# BAL3S.net
KiCad netlist of a schematic drawn in EAGLE
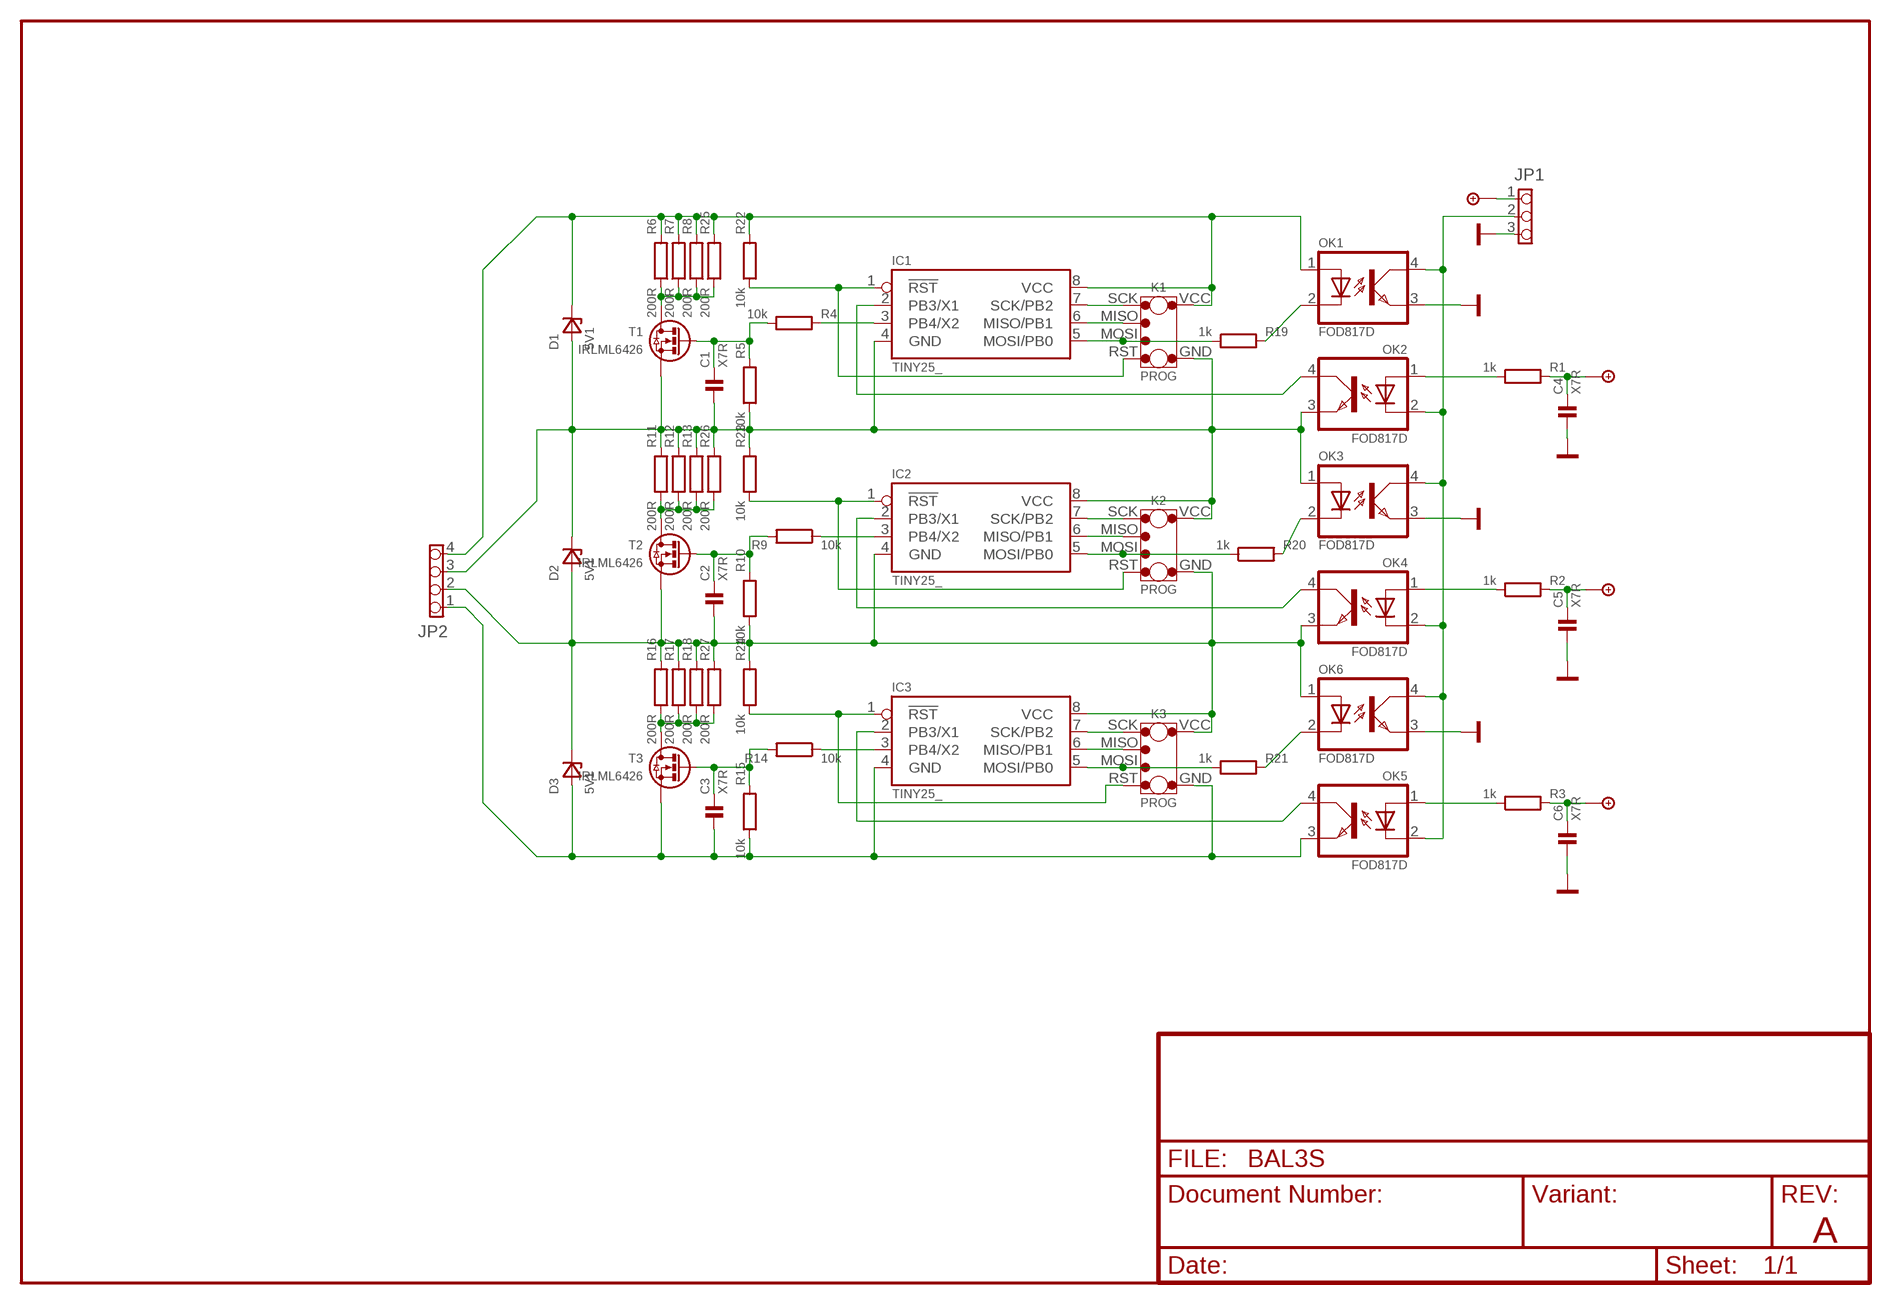
[diagram p0: schematic, sheet 1]

(export (version "E")
  (design (tool "Eeschema 10.0.6"))
  (components
    (comp (ref "C1")
      (value "C0805")
      (footprint "eagle-import:0805")
      (libsource (lib "eagle-import") (part "C0805"))
    )
    (comp (ref "C2")
      (value "C0805")
      (footprint "eagle-import:0805")
      (libsource (lib "eagle-import") (part "C0805"))
    )
    (comp (ref "C3")
      (value "C0805")
      (footprint "eagle-import:0805")
      (libsource (lib "eagle-import") (part "C0805"))
    )
    (comp (ref "C4")
      (value "C0805")
      (footprint "eagle-import:0805")
      (libsource (lib "eagle-import") (part "C0805"))
    )
    (comp (ref "C5")
      (value "C0805")
      (footprint "eagle-import:0805")
      (libsource (lib "eagle-import") (part "C0805"))
    )
    (comp (ref "C6")
      (value "C0805")
      (footprint "eagle-import:0805")
      (libsource (lib "eagle-import") (part "C0805"))
    )
    (comp (ref "D1")
      (value "5V1")
      (footprint "eagle-import:D_MLL41")
      (libsource (lib "eagle-import") (part "D_ZENER_MLL41"))
    )
    (comp (ref "D2")
      (value "5V1")
      (footprint "eagle-import:D_MLL41")
      (libsource (lib "eagle-import") (part "D_ZENER_MLL41"))
    )
    (comp (ref "D3")
      (value "5V1")
      (footprint "eagle-import:D_MLL41")
      (libsource (lib "eagle-import") (part "D_ZENER_MLL41"))
    )
    (comp (ref "IC1")
      (value "TINY25_")
      (footprint "eagle-import:SO08")
      (libsource (lib "eagle-import") (part "TINY25_"))
    )
    (comp (ref "IC2")
      (value "TINY25_")
      (footprint "eagle-import:SO08")
      (libsource (lib "eagle-import") (part "TINY25_"))
    )
    (comp (ref "IC3")
      (value "TINY25_")
      (footprint "eagle-import:SO08")
      (libsource (lib "eagle-import") (part "TINY25_"))
    )
    (comp (ref "JP1")
      (value "PINHD-1X3_254_EDGE")
      (footprint "eagle-import:1X03_254_EDGE")
      (libsource (lib "eagle-import") (part "PINHD-1X3_254_EDGE"))
    )
    (comp (ref "JP2")
      (value "PINHD-1X4_254_EDGE")
      (footprint "eagle-import:1X04_254_EDGE")
      (libsource (lib "eagle-import") (part "PINHD-1X4_254_EDGE"))
    )
    (comp (ref "K1")
      (value "PROG")
      (footprint "eagle-import:PROG")
      (libsource (lib "eagle-import") (part "PROG"))
    )
    (comp (ref "K2")
      (value "PROG")
      (footprint "eagle-import:PROG")
      (libsource (lib "eagle-import") (part "PROG"))
    )
    (comp (ref "K3")
      (value "PROG")
      (footprint "eagle-import:PROG")
      (libsource (lib "eagle-import") (part "PROG"))
    )
    (comp (ref "OK1")
      (value "FOD817D")
      (footprint "eagle-import:SO04")
      (libsource (lib "eagle-import") (part "OC_T_NOBASE"))
    )
    (comp (ref "OK2")
      (value "FOD817D")
      (footprint "eagle-import:SO04")
      (libsource (lib "eagle-import") (part "OC_T_NOBASE"))
    )
    (comp (ref "OK3")
      (value "FOD817D")
      (footprint "eagle-import:SO04")
      (libsource (lib "eagle-import") (part "OC_T_NOBASE"))
    )
    (comp (ref "OK4")
      (value "FOD817D")
      (footprint "eagle-import:SO04")
      (libsource (lib "eagle-import") (part "OC_T_NOBASE"))
    )
    (comp (ref "OK5")
      (value "FOD817D")
      (footprint "eagle-import:SO04")
      (libsource (lib "eagle-import") (part "OC_T_NOBASE"))
    )
    (comp (ref "OK6")
      (value "FOD817D")
      (footprint "eagle-import:SO04")
      (libsource (lib "eagle-import") (part "OC_T_NOBASE"))
    )
    (comp (ref "R1")
      (value "1k")
      (footprint "eagle-import:0805")
      (libsource (lib "eagle-import") (part "R_R0805"))
    )
    (comp (ref "R2")
      (value "1k")
      (footprint "eagle-import:0805")
      (libsource (lib "eagle-import") (part "R_R0805"))
    )
    (comp (ref "R3")
      (value "1k")
      (footprint "eagle-import:0805")
      (libsource (lib "eagle-import") (part "R_R0805"))
    )
    (comp (ref "R4")
      (value "10k")
      (footprint "eagle-import:0805")
      (libsource (lib "eagle-import") (part "R_R0805"))
    )
    (comp (ref "R5")
      (value "10k")
      (footprint "eagle-import:0805")
      (libsource (lib "eagle-import") (part "R_R0805"))
    )
    (comp (ref "R6")
      (value "200R")
      (footprint "eagle-import:0805")
      (libsource (lib "eagle-import") (part "R_R0805"))
    )
    (comp (ref "R7")
      (value "200R")
      (footprint "eagle-import:0805")
      (libsource (lib "eagle-import") (part "R_R0805"))
    )
    (comp (ref "R8")
      (value "200R")
      (footprint "eagle-import:0805")
      (libsource (lib "eagle-import") (part "R_R0805"))
    )
    (comp (ref "R9")
      (value "10k")
      (footprint "eagle-import:0805")
      (libsource (lib "eagle-import") (part "R_R0805"))
    )
    (comp (ref "R10")
      (value "10k")
      (footprint "eagle-import:0805")
      (libsource (lib "eagle-import") (part "R_R0805"))
    )
    (comp (ref "R11")
      (value "200R")
      (footprint "eagle-import:0805")
      (libsource (lib "eagle-import") (part "R_R0805"))
    )
    (comp (ref "R12")
      (value "200R")
      (footprint "eagle-import:0805")
      (libsource (lib "eagle-import") (part "R_R0805"))
    )
    (comp (ref "R13")
      (value "200R")
      (footprint "eagle-import:0805")
      (libsource (lib "eagle-import") (part "R_R0805"))
    )
    (comp (ref "R14")
      (value "10k")
      (footprint "eagle-import:0805")
      (libsource (lib "eagle-import") (part "R_R0805"))
    )
    (comp (ref "R15")
      (value "10k")
      (footprint "eagle-import:0805")
      (libsource (lib "eagle-import") (part "R_R0805"))
    )
    (comp (ref "R16")
      (value "200R")
      (footprint "eagle-import:0805")
      (libsource (lib "eagle-import") (part "R_R0805"))
    )
    (comp (ref "R17")
      (value "200R")
      (footprint "eagle-import:0805")
      (libsource (lib "eagle-import") (part "R_R0805"))
    )
    (comp (ref "R18")
      (value "200R")
      (footprint "eagle-import:0805")
      (libsource (lib "eagle-import") (part "R_R0805"))
    )
    (comp (ref "R19")
      (value "1k")
      (footprint "eagle-import:0805")
      (libsource (lib "eagle-import") (part "R_R0805"))
    )
    (comp (ref "R20")
      (value "1k")
      (footprint "eagle-import:0805")
      (libsource (lib "eagle-import") (part "R_R0805"))
    )
    (comp (ref "R21")
      (value "1k")
      (footprint "eagle-import:0805")
      (libsource (lib "eagle-import") (part "R_R0805"))
    )
    (comp (ref "R22")
      (value "10k")
      (footprint "eagle-import:0805")
      (libsource (lib "eagle-import") (part "R_R0805"))
    )
    (comp (ref "R23")
      (value "10k")
      (footprint "eagle-import:0805")
      (libsource (lib "eagle-import") (part "R_R0805"))
    )
    (comp (ref "R24")
      (value "10k")
      (footprint "eagle-import:0805")
      (libsource (lib "eagle-import") (part "R_R0805"))
    )
    (comp (ref "R25")
      (value "200R")
      (footprint "eagle-import:0805")
      (libsource (lib "eagle-import") (part "R_R0805"))
    )
    (comp (ref "R26")
      (value "200R")
      (footprint "eagle-import:0805")
      (libsource (lib "eagle-import") (part "R_R0805"))
    )
    (comp (ref "R27")
      (value "200R")
      (footprint "eagle-import:0805")
      (libsource (lib "eagle-import") (part "R_R0805"))
    )
    (comp (ref "T1")
      (value "IRLML6426")
      (footprint "eagle-import:SOT23")
      (libsource (lib "eagle-import") (part "_EMOS_N_SOT23_GDS"))
    )
    (comp (ref "T2")
      (value "IRLML6426")
      (footprint "eagle-import:SOT23")
      (libsource (lib "eagle-import") (part "_EMOS_N_SOT23_GDS"))
    )
    (comp (ref "T3")
      (value "IRLML6426")
      (footprint "eagle-import:SOT23")
      (libsource (lib "eagle-import") (part "_EMOS_N_SOT23_GDS"))
    )
  )
  (nets
    (net (code "1") (name "+5V") (class "Default")
      (node (ref "C4") (pin "1") (pinfunction "1_1") (pintype "passive"))
      (node (ref "C5") (pin "1") (pinfunction "1_1") (pintype "passive"))
      (node (ref "C6") (pin "1") (pinfunction "1_1") (pintype "passive"))
      (node (ref "JP1") (pin "1") (pinfunction "1_1") (pintype "passive"))
      (node (ref "R1") (pin "2") (pinfunction "2_2") (pintype "passive"))
      (node (ref "R2") (pin "2") (pinfunction "2_2") (pintype "passive"))
      (node (ref "R3") (pin "2") (pinfunction "2_2") (pintype "passive"))
    )
    (net (code "2") (name "GND") (class "Default")
      (node (ref "C4") (pin "2") (pinfunction "2_2") (pintype "passive"))
      (node (ref "C5") (pin "2") (pinfunction "2_2") (pintype "passive"))
      (node (ref "C6") (pin "2") (pinfunction "2_2") (pintype "passive"))
      (node (ref "JP1") (pin "3") (pinfunction "3_3") (pintype "passive"))
      (node (ref "OK1") (pin "3") (pinfunction "EMIT_3") (pintype "passive"))
      (node (ref "OK3") (pin "3") (pinfunction "EMIT_3") (pintype "passive"))
      (node (ref "OK6") (pin "3") (pinfunction "EMIT_3") (pintype "passive"))
    )
    (net (code "3") (name "Net-(IC1-GND)") (class "Default")
      (node (ref "C1") (pin "2") (pinfunction "2_2") (pintype "passive"))
      (node (ref "D1") (pin "A") (pinfunction "A_A") (pintype "passive"))
      (node (ref "D2") (pin "K") (pinfunction "K_K") (pintype "passive"))
      (node (ref "IC1") (pin "4") (pinfunction "GND_4") (pintype "passive"))
      (node (ref "IC2") (pin "8") (pinfunction "VCC_8") (pintype "passive"))
      (node (ref "JP2") (pin "3") (pinfunction "3_3") (pintype "passive"))
      (node (ref "K1") (pin "GND") (pinfunction "GND_GND") (pintype "passive"))
      (node (ref "K2") (pin "VCC") (pinfunction "VCC_VCC") (pintype "passive"))
      (node (ref "OK2") (pin "3") (pinfunction "EMIT_3") (pintype "passive"))
      (node (ref "OK3") (pin "1") (pinfunction "A_1") (pintype "passive"))
      (node (ref "R11") (pin "2") (pinfunction "2_2") (pintype "passive"))
      (node (ref "R12") (pin "2") (pinfunction "2_2") (pintype "passive"))
      (node (ref "R13") (pin "2") (pinfunction "2_2") (pintype "passive"))
      (node (ref "R23") (pin "2") (pinfunction "2_2") (pintype "passive"))
      (node (ref "R26") (pin "2") (pinfunction "2_2") (pintype "passive"))
      (node (ref "R5") (pin "1") (pinfunction "1_1") (pintype "passive"))
      (node (ref "T1") (pin "3") (pinfunction "S_3") (pintype "passive"))
    )
    (net (code "4") (name "Net-(IC1-MISO{slash}PB1)") (class "Default")
      (node (ref "IC1") (pin "6") (pinfunction "MISO/PB1_6") (pintype "passive"))
      (node (ref "K1") (pin "MISO") (pinfunction "MISO_MISO") (pintype "passive"))
    )
    (net (code "5") (name "Net-(IC1-MOSI{slash}PB0)") (class "Default")
      (node (ref "IC1") (pin "5") (pinfunction "MOSI/PB0_5") (pintype "passive"))
      (node (ref "K1") (pin "MOSI") (pinfunction "MOSI_MOSI") (pintype "passive"))
      (node (ref "R19") (pin "1") (pinfunction "1_1") (pintype "passive"))
    )
    (net (code "6") (name "Net-(IC1-PB3{slash}X1)") (class "Default")
      (node (ref "IC1") (pin "2") (pinfunction "PB3/X1_2") (pintype "passive"))
      (node (ref "OK2") (pin "4") (pinfunction "COL_4") (pintype "passive"))
    )
    (net (code "7") (name "Net-(IC1-PB4{slash}X2)") (class "Default")
      (node (ref "IC1") (pin "3") (pinfunction "PB4/X2_3") (pintype "passive"))
      (node (ref "R4") (pin "2") (pinfunction "2_2") (pintype "passive"))
    )
    (net (code "8") (name "Net-(IC1-SCK{slash}PB2)") (class "Default")
      (node (ref "IC1") (pin "7") (pinfunction "SCK/PB2_7") (pintype "passive"))
      (node (ref "K1") (pin "SCK") (pinfunction "SCK_SCK") (pintype "passive"))
    )
    (net (code "9") (name "Net-(IC1-VCC)") (class "Default")
      (node (ref "D1") (pin "K") (pinfunction "K_K") (pintype "passive"))
      (node (ref "IC1") (pin "8") (pinfunction "VCC_8") (pintype "passive"))
      (node (ref "JP2") (pin "4") (pinfunction "4_4") (pintype "passive"))
      (node (ref "K1") (pin "VCC") (pinfunction "VCC_VCC") (pintype "passive"))
      (node (ref "OK1") (pin "1") (pinfunction "A_1") (pintype "passive"))
      (node (ref "R22") (pin "2") (pinfunction "2_2") (pintype "passive"))
      (node (ref "R25") (pin "2") (pinfunction "2_2") (pintype "passive"))
      (node (ref "R6") (pin "2") (pinfunction "2_2") (pintype "passive"))
      (node (ref "R7") (pin "2") (pinfunction "2_2") (pintype "passive"))
      (node (ref "R8") (pin "2") (pinfunction "2_2") (pintype "passive"))
    )
    (net (code "10") (name "Net-(IC1-~{RST})") (class "Default")
      (node (ref "IC1") (pin "1") (pinfunction "~{RST}_1") (pintype "passive"))
      (node (ref "K1") (pin "RST") (pinfunction "RST_RST") (pintype "passive"))
      (node (ref "R22") (pin "1") (pinfunction "1_1") (pintype "passive"))
    )
    (net (code "11") (name "Net-(IC2-GND)") (class "Default")
      (node (ref "C2") (pin "2") (pinfunction "2_2") (pintype "passive"))
      (node (ref "D2") (pin "A") (pinfunction "A_A") (pintype "passive"))
      (node (ref "D3") (pin "K") (pinfunction "K_K") (pintype "passive"))
      (node (ref "IC2") (pin "4") (pinfunction "GND_4") (pintype "passive"))
      (node (ref "IC3") (pin "8") (pinfunction "VCC_8") (pintype "passive"))
      (node (ref "JP2") (pin "2") (pinfunction "2_2") (pintype "passive"))
      (node (ref "K2") (pin "GND") (pinfunction "GND_GND") (pintype "passive"))
      (node (ref "K3") (pin "VCC") (pinfunction "VCC_VCC") (pintype "passive"))
      (node (ref "OK4") (pin "3") (pinfunction "EMIT_3") (pintype "passive"))
      (node (ref "OK6") (pin "1") (pinfunction "A_1") (pintype "passive"))
      (node (ref "R10") (pin "1") (pinfunction "1_1") (pintype "passive"))
      (node (ref "R16") (pin "2") (pinfunction "2_2") (pintype "passive"))
      (node (ref "R17") (pin "2") (pinfunction "2_2") (pintype "passive"))
      (node (ref "R18") (pin "2") (pinfunction "2_2") (pintype "passive"))
      (node (ref "R24") (pin "2") (pinfunction "2_2") (pintype "passive"))
      (node (ref "R27") (pin "2") (pinfunction "2_2") (pintype "passive"))
      (node (ref "T2") (pin "3") (pinfunction "S_3") (pintype "passive"))
    )
    (net (code "12") (name "Net-(IC2-MISO{slash}PB1)") (class "Default")
      (node (ref "IC2") (pin "6") (pinfunction "MISO/PB1_6") (pintype "passive"))
      (node (ref "K2") (pin "MISO") (pinfunction "MISO_MISO") (pintype "passive"))
    )
    (net (code "13") (name "Net-(IC2-MOSI{slash}PB0)") (class "Default")
      (node (ref "IC2") (pin "5") (pinfunction "MOSI/PB0_5") (pintype "passive"))
      (node (ref "K2") (pin "MOSI") (pinfunction "MOSI_MOSI") (pintype "passive"))
      (node (ref "R20") (pin "1") (pinfunction "1_1") (pintype "passive"))
    )
    (net (code "14") (name "Net-(IC2-PB3{slash}X1)") (class "Default")
      (node (ref "IC2") (pin "2") (pinfunction "PB3/X1_2") (pintype "passive"))
      (node (ref "OK4") (pin "4") (pinfunction "COL_4") (pintype "passive"))
    )
    (net (code "15") (name "Net-(IC2-PB4{slash}X2)") (class "Default")
      (node (ref "IC2") (pin "3") (pinfunction "PB4/X2_3") (pintype "passive"))
      (node (ref "R9") (pin "1") (pinfunction "1_1") (pintype "passive"))
    )
    (net (code "16") (name "Net-(IC2-SCK{slash}PB2)") (class "Default")
      (node (ref "IC2") (pin "7") (pinfunction "SCK/PB2_7") (pintype "passive"))
      (node (ref "K2") (pin "SCK") (pinfunction "SCK_SCK") (pintype "passive"))
    )
    (net (code "17") (name "Net-(IC2-~{RST})") (class "Default")
      (node (ref "IC2") (pin "1") (pinfunction "~{RST}_1") (pintype "passive"))
      (node (ref "K2") (pin "RST") (pinfunction "RST_RST") (pintype "passive"))
      (node (ref "R23") (pin "1") (pinfunction "1_1") (pintype "passive"))
    )
    (net (code "18") (name "Net-(IC3-GND)") (class "Default")
      (node (ref "C3") (pin "2") (pinfunction "2_2") (pintype "passive"))
      (node (ref "D3") (pin "A") (pinfunction "A_A") (pintype "passive"))
      (node (ref "IC3") (pin "4") (pinfunction "GND_4") (pintype "passive"))
      (node (ref "JP2") (pin "1") (pinfunction "1_1") (pintype "passive"))
      (node (ref "K3") (pin "GND") (pinfunction "GND_GND") (pintype "passive"))
      (node (ref "OK5") (pin "3") (pinfunction "EMIT_3") (pintype "passive"))
      (node (ref "R15") (pin "1") (pinfunction "1_1") (pintype "passive"))
      (node (ref "T3") (pin "3") (pinfunction "S_3") (pintype "passive"))
    )
    (net (code "19") (name "Net-(IC3-MISO{slash}PB1)") (class "Default")
      (node (ref "IC3") (pin "6") (pinfunction "MISO/PB1_6") (pintype "passive"))
      (node (ref "K3") (pin "MISO") (pinfunction "MISO_MISO") (pintype "passive"))
    )
    (net (code "20") (name "Net-(IC3-MOSI{slash}PB0)") (class "Default")
      (node (ref "IC3") (pin "5") (pinfunction "MOSI/PB0_5") (pintype "passive"))
      (node (ref "K3") (pin "MOSI") (pinfunction "MOSI_MOSI") (pintype "passive"))
      (node (ref "R21") (pin "1") (pinfunction "1_1") (pintype "passive"))
    )
    (net (code "21") (name "Net-(IC3-PB3{slash}X1)") (class "Default")
      (node (ref "IC3") (pin "2") (pinfunction "PB3/X1_2") (pintype "passive"))
      (node (ref "OK5") (pin "4") (pinfunction "COL_4") (pintype "passive"))
    )
    (net (code "22") (name "Net-(IC3-PB4{slash}X2)") (class "Default")
      (node (ref "IC3") (pin "3") (pinfunction "PB4/X2_3") (pintype "passive"))
      (node (ref "R14") (pin "1") (pinfunction "1_1") (pintype "passive"))
    )
    (net (code "23") (name "Net-(IC3-SCK{slash}PB2)") (class "Default")
      (node (ref "IC3") (pin "7") (pinfunction "SCK/PB2_7") (pintype "passive"))
      (node (ref "K3") (pin "SCK") (pinfunction "SCK_SCK") (pintype "passive"))
    )
    (net (code "24") (name "Net-(IC3-~{RST})") (class "Default")
      (node (ref "IC3") (pin "1") (pinfunction "~{RST}_1") (pintype "passive"))
      (node (ref "K3") (pin "RST") (pinfunction "RST_RST") (pintype "passive"))
      (node (ref "R24") (pin "1") (pinfunction "1_1") (pintype "passive"))
    )
    (net (code "25") (name "Net-(OK1-C)") (class "Default")
      (node (ref "OK1") (pin "2") (pinfunction "C_2") (pintype "passive"))
      (node (ref "R19") (pin "2") (pinfunction "2_2") (pintype "passive"))
    )
    (net (code "26") (name "Net-(OK1-COL)") (class "Default")
      (node (ref "JP1") (pin "2") (pinfunction "2_2") (pintype "passive"))
      (node (ref "OK1") (pin "4") (pinfunction "COL_4") (pintype "passive"))
      (node (ref "OK2") (pin "2") (pinfunction "C_2") (pintype "passive"))
      (node (ref "OK3") (pin "4") (pinfunction "COL_4") (pintype "passive"))
      (node (ref "OK4") (pin "2") (pinfunction "C_2") (pintype "passive"))
      (node (ref "OK5") (pin "2") (pinfunction "C_2") (pintype "passive"))
      (node (ref "OK6") (pin "4") (pinfunction "COL_4") (pintype "passive"))
    )
    (net (code "27") (name "Net-(OK2-A)") (class "Default")
      (node (ref "OK2") (pin "1") (pinfunction "A_1") (pintype "passive"))
      (node (ref "R1") (pin "1") (pinfunction "1_1") (pintype "passive"))
    )
    (net (code "28") (name "Net-(OK3-C)") (class "Default")
      (node (ref "OK3") (pin "2") (pinfunction "C_2") (pintype "passive"))
      (node (ref "R20") (pin "2") (pinfunction "2_2") (pintype "passive"))
    )
    (net (code "29") (name "Net-(OK4-A)") (class "Default")
      (node (ref "OK4") (pin "1") (pinfunction "A_1") (pintype "passive"))
      (node (ref "R2") (pin "1") (pinfunction "1_1") (pintype "passive"))
    )
    (net (code "30") (name "Net-(OK5-A)") (class "Default")
      (node (ref "OK5") (pin "1") (pinfunction "A_1") (pintype "passive"))
      (node (ref "R3") (pin "1") (pinfunction "1_1") (pintype "passive"))
    )
    (net (code "31") (name "Net-(OK6-C)") (class "Default")
      (node (ref "OK6") (pin "2") (pinfunction "C_2") (pintype "passive"))
      (node (ref "R21") (pin "2") (pinfunction "2_2") (pintype "passive"))
    )
    (net (code "32") (name "Net-(T1-D)") (class "Default")
      (node (ref "R25") (pin "1") (pinfunction "1_1") (pintype "passive"))
      (node (ref "R6") (pin "1") (pinfunction "1_1") (pintype "passive"))
      (node (ref "R7") (pin "1") (pinfunction "1_1") (pintype "passive"))
      (node (ref "R8") (pin "1") (pinfunction "1_1") (pintype "passive"))
      (node (ref "T1") (pin "2") (pinfunction "D_2") (pintype "passive"))
    )
    (net (code "33") (name "Net-(T1-G)") (class "Default")
      (node (ref "C1") (pin "1") (pinfunction "1_1") (pintype "passive"))
      (node (ref "R4") (pin "1") (pinfunction "1_1") (pintype "passive"))
      (node (ref "R5") (pin "2") (pinfunction "2_2") (pintype "passive"))
      (node (ref "T1") (pin "1") (pinfunction "G_1") (pintype "passive"))
    )
    (net (code "34") (name "Net-(T2-D)") (class "Default")
      (node (ref "R11") (pin "1") (pinfunction "1_1") (pintype "passive"))
      (node (ref "R12") (pin "1") (pinfunction "1_1") (pintype "passive"))
      (node (ref "R13") (pin "1") (pinfunction "1_1") (pintype "passive"))
      (node (ref "R26") (pin "1") (pinfunction "1_1") (pintype "passive"))
      (node (ref "T2") (pin "2") (pinfunction "D_2") (pintype "passive"))
    )
    (net (code "35") (name "Net-(T2-G)") (class "Default")
      (node (ref "C2") (pin "1") (pinfunction "1_1") (pintype "passive"))
      (node (ref "R10") (pin "2") (pinfunction "2_2") (pintype "passive"))
      (node (ref "R9") (pin "2") (pinfunction "2_2") (pintype "passive"))
      (node (ref "T2") (pin "1") (pinfunction "G_1") (pintype "passive"))
    )
    (net (code "36") (name "Net-(T3-D)") (class "Default")
      (node (ref "R16") (pin "1") (pinfunction "1_1") (pintype "passive"))
      (node (ref "R17") (pin "1") (pinfunction "1_1") (pintype "passive"))
      (node (ref "R18") (pin "1") (pinfunction "1_1") (pintype "passive"))
      (node (ref "R27") (pin "1") (pinfunction "1_1") (pintype "passive"))
      (node (ref "T3") (pin "2") (pinfunction "D_2") (pintype "passive"))
    )
    (net (code "37") (name "Net-(T3-G)") (class "Default")
      (node (ref "C3") (pin "1") (pinfunction "1_1") (pintype "passive"))
      (node (ref "R14") (pin "2") (pinfunction "2_2") (pintype "passive"))
      (node (ref "R15") (pin "2") (pinfunction "2_2") (pintype "passive"))
      (node (ref "T3") (pin "1") (pinfunction "G_1") (pintype "passive"))
    )
  )
)
